# FPGA_Power_ConnectionSchematic.net
KiCad netlist of a schematic drawn in Altium Designer
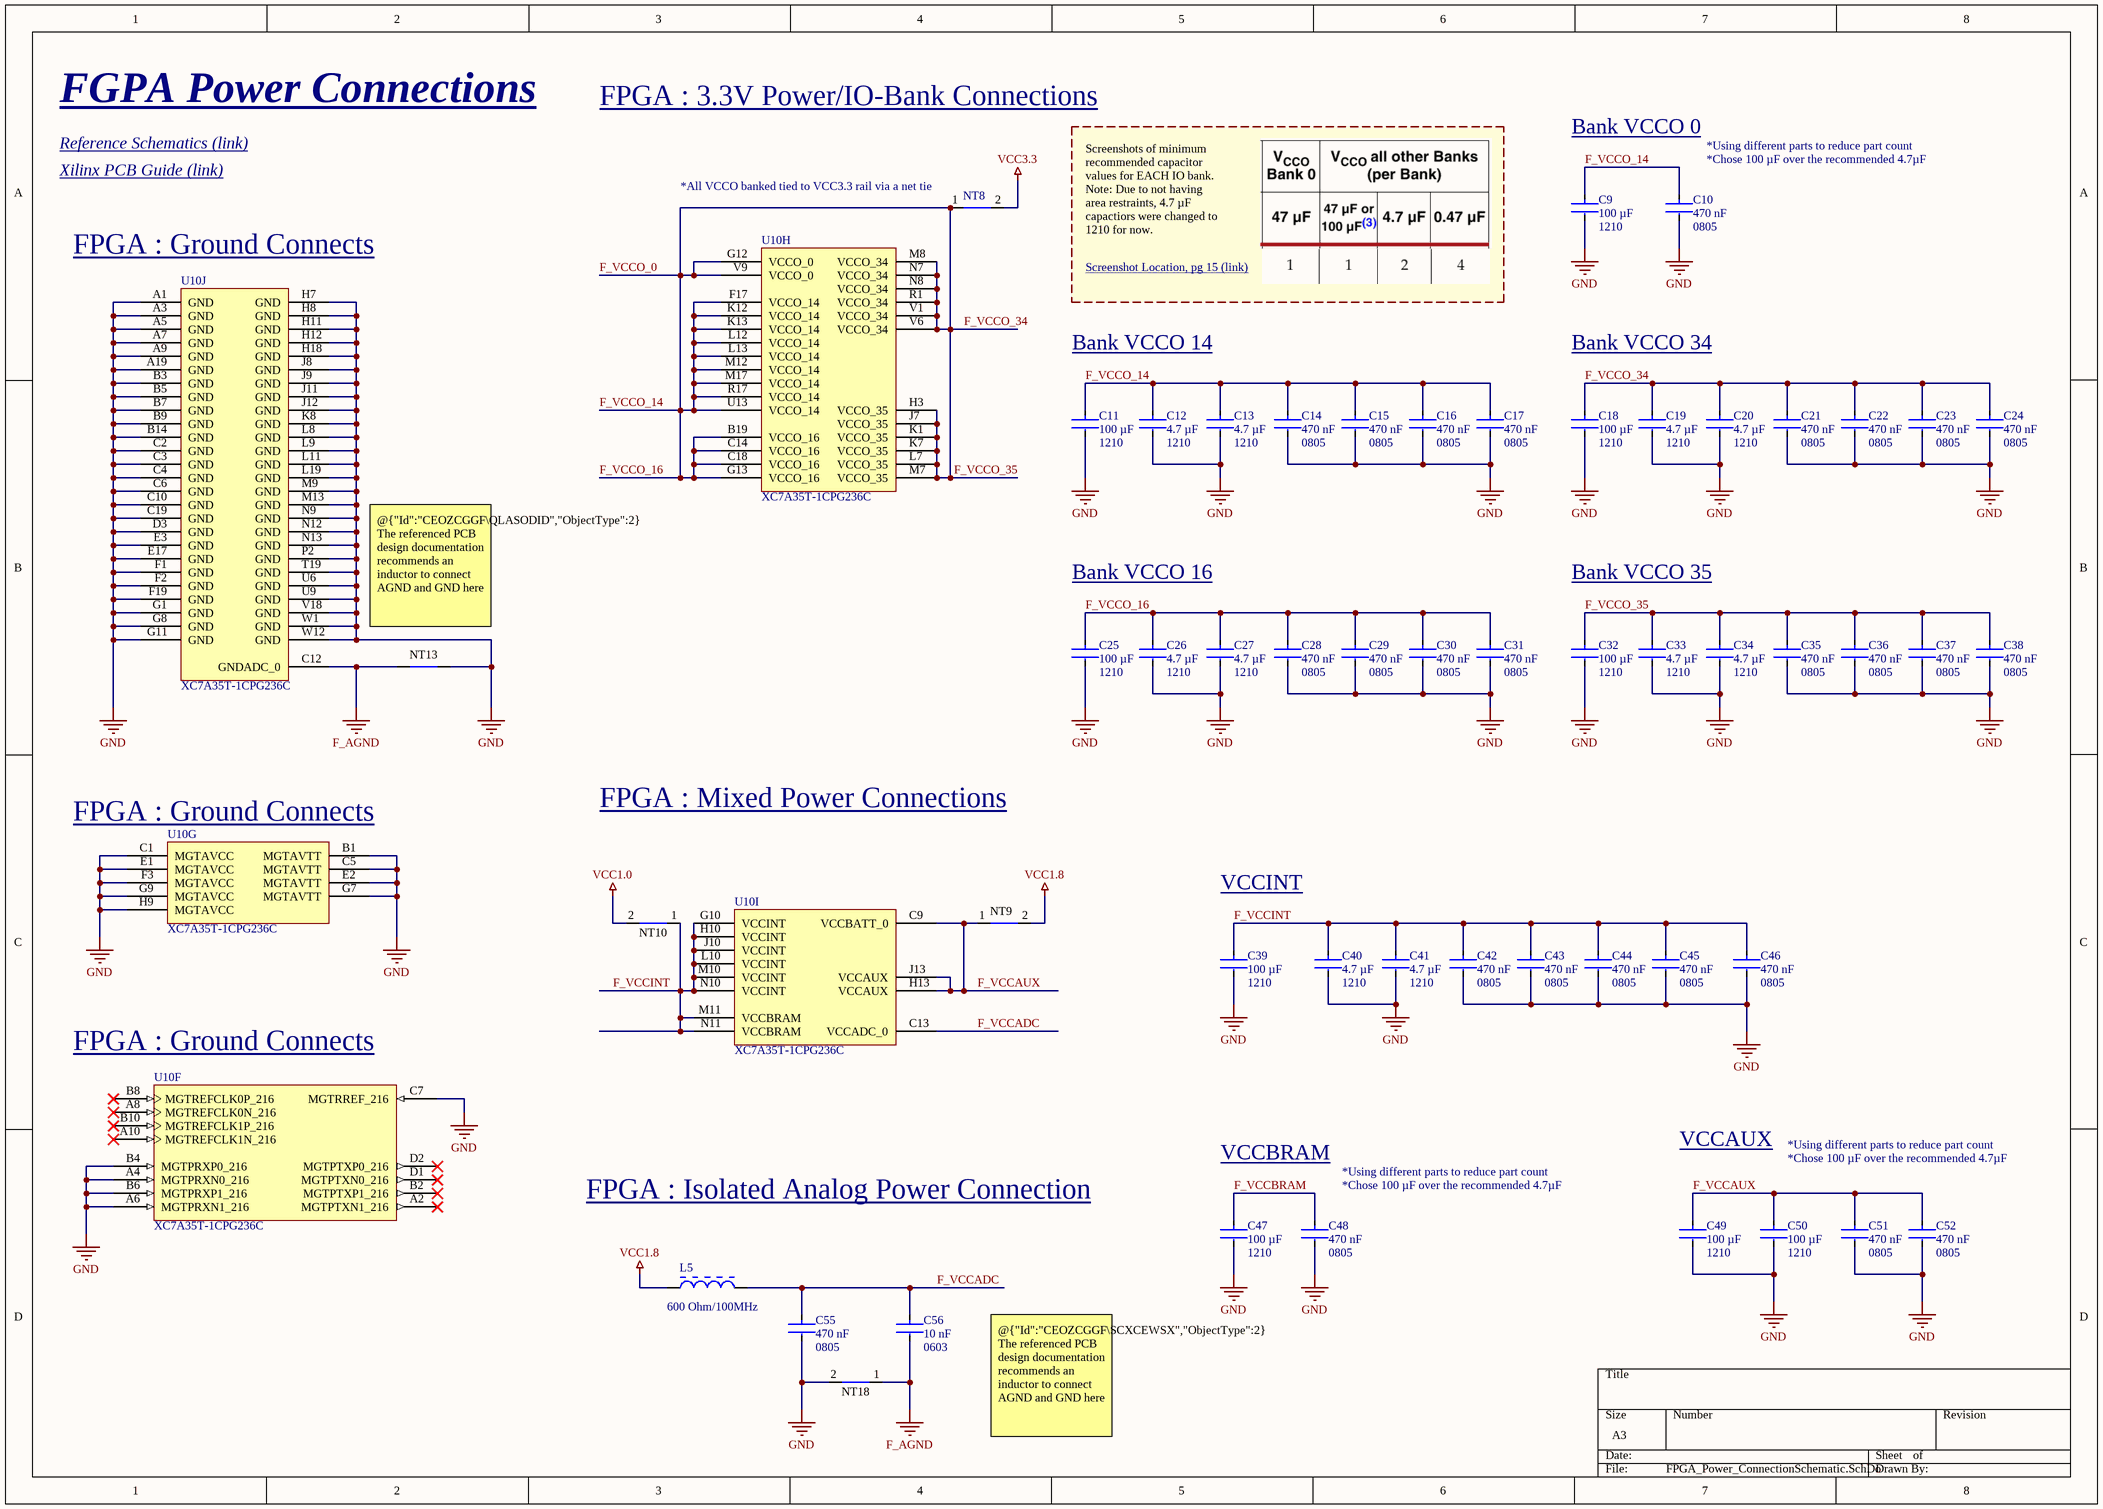
[diagram p0: FPGA_Power_ConnectionSchematic.SchDoc]

(export (version "E")
  (design (tool "Eeschema 10.0.6"))
  (components
    (comp (ref "C9")
      (value "CL32A107MQVNNNE")
      (footprint "FP-CL32-IPC_C")
      (description "CAP CER 100UF 6.3V X5R 1210")
      (fields
        (field (name "VOLTAGE") "6.3V")
        (field (name "TOLERANCE") "20%")
        (field (name "CASE CODE (IMPERIAL)") "1210")
        (field (name "CAPACITANCE") "100 µF")
      )
      (libsource (lib "Altium Content Vault") (part "b4654b650e69147ec39a6b967a45e02"))
    )
    (comp (ref "C10")
      (value "CGA4J3X7R1H474M125AE")
      (footprint "FP-CGA4J-IPC_A")
      (description "Cap Ceramic 470nF 50V X7R 20% Pad SMD 0805 +125°C Automotive T/R")
      (fields
        (field (name "CASE CODE (IMPERIAL)") "0805")
        (field (name "TOLERANCE") "20%")
        (field (name "CAPACITANCE") "470 nF")
      )
      (libsource (lib "Altium Content Vault") (part "b4654b650e69147ec39a6b967a45e02"))
    )
    (comp (ref "C11")
      (value "CL32A107MQVNNNE")
      (footprint "FP-CL32-IPC_C")
      (description "CAP CER 100UF 6.3V X5R 1210")
      (fields
        (field (name "VOLTAGE") "6.3V")
        (field (name "TOLERANCE") "20%")
        (field (name "CASE CODE (IMPERIAL)") "1210")
        (field (name "CAPACITANCE") "100 µF")
      )
      (libsource (lib "Altium Content Vault") (part "b4654b650e69147ec39a6b967a45e02"))
    )
    (comp (ref "C12")
      (value "12105C475K4Z2A")
      (footprint "FP-1210-L_3_3_0_4-W_2_5_0-IPC_B")
      (description "Automotive Ceramic Capacitor, 1210, 4.7uF, 10%, X7R, 15%, 50V")
      (fields
        (field (name "TOLERANCE") "10%")
        (field (name "CASE/PACKAGE") "1210")
        (field (name "CAPACITANCE") "4.7 µF")
      )
      (libsource (lib "Altium Content Vault") (part "b4654b650e69147ec39a6b967a45e02"))
    )
    (comp (ref "C13")
      (value "12105C475K4Z2A")
      (footprint "FP-1210-L_3_3_0_4-W_2_5_0-IPC_B")
      (description "Automotive Ceramic Capacitor, 1210, 4.7uF, 10%, X7R, 15%, 50V")
      (fields
        (field (name "TOLERANCE") "10%")
        (field (name "CASE/PACKAGE") "1210")
        (field (name "CAPACITANCE") "4.7 µF")
      )
      (libsource (lib "Altium Content Vault") (part "b4654b650e69147ec39a6b967a45e02"))
    )
    (comp (ref "C14")
      (value "CGA4J3X7R1H474M125AE")
      (footprint "FP-CGA4J-IPC_A")
      (description "Cap Ceramic 470nF 50V X7R 20% Pad SMD 0805 +125°C Automotive T/R")
      (fields
        (field (name "CASE CODE (IMPERIAL)") "0805")
        (field (name "TOLERANCE") "20%")
        (field (name "CAPACITANCE") "470 nF")
      )
      (libsource (lib "Altium Content Vault") (part "b4654b650e69147ec39a6b967a45e02"))
    )
    (comp (ref "C15")
      (value "CGA4J3X7R1H474M125AE")
      (footprint "FP-CGA4J-IPC_A")
      (description "Cap Ceramic 470nF 50V X7R 20% Pad SMD 0805 +125°C Automotive T/R")
      (fields
        (field (name "CASE CODE (IMPERIAL)") "0805")
        (field (name "TOLERANCE") "20%")
        (field (name "CAPACITANCE") "470 nF")
      )
      (libsource (lib "Altium Content Vault") (part "b4654b650e69147ec39a6b967a45e02"))
    )
    (comp (ref "C16")
      (value "CGA4J3X7R1H474M125AE")
      (footprint "FP-CGA4J-IPC_A")
      (description "Cap Ceramic 470nF 50V X7R 20% Pad SMD 0805 +125°C Automotive T/R")
      (fields
        (field (name "CASE CODE (IMPERIAL)") "0805")
        (field (name "TOLERANCE") "20%")
        (field (name "CAPACITANCE") "470 nF")
      )
      (libsource (lib "Altium Content Vault") (part "b4654b650e69147ec39a6b967a45e02"))
    )
    (comp (ref "C17")
      (value "CGA4J3X7R1H474M125AE")
      (footprint "FP-CGA4J-IPC_A")
      (description "Cap Ceramic 470nF 50V X7R 20% Pad SMD 0805 +125°C Automotive T/R")
      (fields
        (field (name "CASE CODE (IMPERIAL)") "0805")
        (field (name "TOLERANCE") "20%")
        (field (name "CAPACITANCE") "470 nF")
      )
      (libsource (lib "Altium Content Vault") (part "b4654b650e69147ec39a6b967a45e02"))
    )
    (comp (ref "C18")
      (value "CL32A107MQVNNNE")
      (footprint "FP-CL32-IPC_C")
      (description "CAP CER 100UF 6.3V X5R 1210")
      (fields
        (field (name "VOLTAGE") "6.3V")
        (field (name "TOLERANCE") "20%")
        (field (name "CASE CODE (IMPERIAL)") "1210")
        (field (name "CAPACITANCE") "100 µF")
      )
      (libsource (lib "Altium Content Vault") (part "b4654b650e69147ec39a6b967a45e02"))
    )
    (comp (ref "C19")
      (value "12105C475K4Z2A")
      (footprint "FP-1210-L_3_3_0_4-W_2_5_0-IPC_B")
      (description "Automotive Ceramic Capacitor, 1210, 4.7uF, 10%, X7R, 15%, 50V")
      (fields
        (field (name "TOLERANCE") "10%")
        (field (name "CASE/PACKAGE") "1210")
        (field (name "CAPACITANCE") "4.7 µF")
      )
      (libsource (lib "Altium Content Vault") (part "b4654b650e69147ec39a6b967a45e02"))
    )
    (comp (ref "C20")
      (value "12105C475K4Z2A")
      (footprint "FP-1210-L_3_3_0_4-W_2_5_0-IPC_B")
      (description "Automotive Ceramic Capacitor, 1210, 4.7uF, 10%, X7R, 15%, 50V")
      (fields
        (field (name "TOLERANCE") "10%")
        (field (name "CASE/PACKAGE") "1210")
        (field (name "CAPACITANCE") "4.7 µF")
      )
      (libsource (lib "Altium Content Vault") (part "b4654b650e69147ec39a6b967a45e02"))
    )
    (comp (ref "C21")
      (value "CGA4J3X7R1H474M125AE")
      (footprint "FP-CGA4J-IPC_A")
      (description "Cap Ceramic 470nF 50V X7R 20% Pad SMD 0805 +125°C Automotive T/R")
      (fields
        (field (name "CASE CODE (IMPERIAL)") "0805")
        (field (name "TOLERANCE") "20%")
        (field (name "CAPACITANCE") "470 nF")
      )
      (libsource (lib "Altium Content Vault") (part "b4654b650e69147ec39a6b967a45e02"))
    )
    (comp (ref "C22")
      (value "CGA4J3X7R1H474M125AE")
      (footprint "FP-CGA4J-IPC_A")
      (description "Cap Ceramic 470nF 50V X7R 20% Pad SMD 0805 +125°C Automotive T/R")
      (fields
        (field (name "CASE CODE (IMPERIAL)") "0805")
        (field (name "TOLERANCE") "20%")
        (field (name "CAPACITANCE") "470 nF")
      )
      (libsource (lib "Altium Content Vault") (part "b4654b650e69147ec39a6b967a45e02"))
    )
    (comp (ref "C23")
      (value "CGA4J3X7R1H474M125AE")
      (footprint "FP-CGA4J-IPC_A")
      (description "Cap Ceramic 470nF 50V X7R 20% Pad SMD 0805 +125°C Automotive T/R")
      (fields
        (field (name "CASE CODE (IMPERIAL)") "0805")
        (field (name "TOLERANCE") "20%")
        (field (name "CAPACITANCE") "470 nF")
      )
      (libsource (lib "Altium Content Vault") (part "b4654b650e69147ec39a6b967a45e02"))
    )
    (comp (ref "C24")
      (value "CGA4J3X7R1H474M125AE")
      (footprint "FP-CGA4J-IPC_A")
      (description "Cap Ceramic 470nF 50V X7R 20% Pad SMD 0805 +125°C Automotive T/R")
      (fields
        (field (name "CASE CODE (IMPERIAL)") "0805")
        (field (name "TOLERANCE") "20%")
        (field (name "CAPACITANCE") "470 nF")
      )
      (libsource (lib "Altium Content Vault") (part "b4654b650e69147ec39a6b967a45e02"))
    )
    (comp (ref "C25")
      (value "CL32A107MQVNNNE")
      (footprint "FP-CL32-IPC_C")
      (description "CAP CER 100UF 6.3V X5R 1210")
      (fields
        (field (name "VOLTAGE") "6.3V")
        (field (name "TOLERANCE") "20%")
        (field (name "CASE CODE (IMPERIAL)") "1210")
        (field (name "CAPACITANCE") "100 µF")
      )
      (libsource (lib "Altium Content Vault") (part "b4654b650e69147ec39a6b967a45e02"))
    )
    (comp (ref "C26")
      (value "12105C475K4Z2A")
      (footprint "FP-1210-L_3_3_0_4-W_2_5_0-IPC_B")
      (description "Automotive Ceramic Capacitor, 1210, 4.7uF, 10%, X7R, 15%, 50V")
      (fields
        (field (name "TOLERANCE") "10%")
        (field (name "CASE/PACKAGE") "1210")
        (field (name "CAPACITANCE") "4.7 µF")
      )
      (libsource (lib "Altium Content Vault") (part "b4654b650e69147ec39a6b967a45e02"))
    )
    (comp (ref "C27")
      (value "12105C475K4Z2A")
      (footprint "FP-1210-L_3_3_0_4-W_2_5_0-IPC_B")
      (description "Automotive Ceramic Capacitor, 1210, 4.7uF, 10%, X7R, 15%, 50V")
      (fields
        (field (name "TOLERANCE") "10%")
        (field (name "CASE/PACKAGE") "1210")
        (field (name "CAPACITANCE") "4.7 µF")
      )
      (libsource (lib "Altium Content Vault") (part "b4654b650e69147ec39a6b967a45e02"))
    )
    (comp (ref "C28")
      (value "CGA4J3X7R1H474M125AE")
      (footprint "FP-CGA4J-IPC_A")
      (description "Cap Ceramic 470nF 50V X7R 20% Pad SMD 0805 +125°C Automotive T/R")
      (fields
        (field (name "CASE CODE (IMPERIAL)") "0805")
        (field (name "TOLERANCE") "20%")
        (field (name "CAPACITANCE") "470 nF")
      )
      (libsource (lib "Altium Content Vault") (part "b4654b650e69147ec39a6b967a45e02"))
    )
    (comp (ref "C29")
      (value "CGA4J3X7R1H474M125AE")
      (footprint "FP-CGA4J-IPC_A")
      (description "Cap Ceramic 470nF 50V X7R 20% Pad SMD 0805 +125°C Automotive T/R")
      (fields
        (field (name "CASE CODE (IMPERIAL)") "0805")
        (field (name "TOLERANCE") "20%")
        (field (name "CAPACITANCE") "470 nF")
      )
      (libsource (lib "Altium Content Vault") (part "b4654b650e69147ec39a6b967a45e02"))
    )
    (comp (ref "C30")
      (value "CGA4J3X7R1H474M125AE")
      (footprint "FP-CGA4J-IPC_A")
      (description "Cap Ceramic 470nF 50V X7R 20% Pad SMD 0805 +125°C Automotive T/R")
      (fields
        (field (name "CASE CODE (IMPERIAL)") "0805")
        (field (name "TOLERANCE") "20%")
        (field (name "CAPACITANCE") "470 nF")
      )
      (libsource (lib "Altium Content Vault") (part "b4654b650e69147ec39a6b967a45e02"))
    )
    (comp (ref "C31")
      (value "CGA4J3X7R1H474M125AE")
      (footprint "FP-CGA4J-IPC_A")
      (description "Cap Ceramic 470nF 50V X7R 20% Pad SMD 0805 +125°C Automotive T/R")
      (fields
        (field (name "CASE CODE (IMPERIAL)") "0805")
        (field (name "TOLERANCE") "20%")
        (field (name "CAPACITANCE") "470 nF")
      )
      (libsource (lib "Altium Content Vault") (part "b4654b650e69147ec39a6b967a45e02"))
    )
    (comp (ref "C32")
      (value "CL32A107MQVNNNE")
      (footprint "FP-CL32-IPC_C")
      (description "CAP CER 100UF 6.3V X5R 1210")
      (fields
        (field (name "VOLTAGE") "6.3V")
        (field (name "TOLERANCE") "20%")
        (field (name "CASE CODE (IMPERIAL)") "1210")
        (field (name "CAPACITANCE") "100 µF")
      )
      (libsource (lib "Altium Content Vault") (part "b4654b650e69147ec39a6b967a45e02"))
    )
    (comp (ref "C33")
      (value "12105C475K4Z2A")
      (footprint "FP-1210-L_3_3_0_4-W_2_5_0-IPC_B")
      (description "Automotive Ceramic Capacitor, 1210, 4.7uF, 10%, X7R, 15%, 50V")
      (fields
        (field (name "TOLERANCE") "10%")
        (field (name "CASE/PACKAGE") "1210")
        (field (name "CAPACITANCE") "4.7 µF")
      )
      (libsource (lib "Altium Content Vault") (part "b4654b650e69147ec39a6b967a45e02"))
    )
    (comp (ref "C34")
      (value "12105C475K4Z2A")
      (footprint "FP-1210-L_3_3_0_4-W_2_5_0-IPC_B")
      (description "Automotive Ceramic Capacitor, 1210, 4.7uF, 10%, X7R, 15%, 50V")
      (fields
        (field (name "TOLERANCE") "10%")
        (field (name "CASE/PACKAGE") "1210")
        (field (name "CAPACITANCE") "4.7 µF")
      )
      (libsource (lib "Altium Content Vault") (part "b4654b650e69147ec39a6b967a45e02"))
    )
    (comp (ref "C35")
      (value "CGA4J3X7R1H474M125AE")
      (footprint "FP-CGA4J-IPC_A")
      (description "Cap Ceramic 470nF 50V X7R 20% Pad SMD 0805 +125°C Automotive T/R")
      (fields
        (field (name "CASE CODE (IMPERIAL)") "0805")
        (field (name "TOLERANCE") "20%")
        (field (name "CAPACITANCE") "470 nF")
      )
      (libsource (lib "Altium Content Vault") (part "b4654b650e69147ec39a6b967a45e02"))
    )
    (comp (ref "C36")
      (value "CGA4J3X7R1H474M125AE")
      (footprint "FP-CGA4J-IPC_A")
      (description "Cap Ceramic 470nF 50V X7R 20% Pad SMD 0805 +125°C Automotive T/R")
      (fields
        (field (name "CASE CODE (IMPERIAL)") "0805")
        (field (name "TOLERANCE") "20%")
        (field (name "CAPACITANCE") "470 nF")
      )
      (libsource (lib "Altium Content Vault") (part "b4654b650e69147ec39a6b967a45e02"))
    )
    (comp (ref "C37")
      (value "CGA4J3X7R1H474M125AE")
      (footprint "FP-CGA4J-IPC_A")
      (description "Cap Ceramic 470nF 50V X7R 20% Pad SMD 0805 +125°C Automotive T/R")
      (fields
        (field (name "CASE CODE (IMPERIAL)") "0805")
        (field (name "TOLERANCE") "20%")
        (field (name "CAPACITANCE") "470 nF")
      )
      (libsource (lib "Altium Content Vault") (part "b4654b650e69147ec39a6b967a45e02"))
    )
    (comp (ref "C38")
      (value "CGA4J3X7R1H474M125AE")
      (footprint "FP-CGA4J-IPC_A")
      (description "Cap Ceramic 470nF 50V X7R 20% Pad SMD 0805 +125°C Automotive T/R")
      (fields
        (field (name "CASE CODE (IMPERIAL)") "0805")
        (field (name "TOLERANCE") "20%")
        (field (name "CAPACITANCE") "470 nF")
      )
      (libsource (lib "Altium Content Vault") (part "b4654b650e69147ec39a6b967a45e02"))
    )
    (comp (ref "C39")
      (value "CL32A107MQVNNNE")
      (footprint "FP-CL32-IPC_C")
      (description "CAP CER 100UF 6.3V X5R 1210")
      (fields
        (field (name "VOLTAGE") "6.3V")
        (field (name "TOLERANCE") "20%")
        (field (name "CASE CODE (IMPERIAL)") "1210")
        (field (name "CAPACITANCE") "100 µF")
      )
      (libsource (lib "Altium Content Vault") (part "b4654b650e69147ec39a6b967a45e02"))
    )
    (comp (ref "C40")
      (value "12105C475K4Z2A")
      (footprint "FP-1210-L_3_3_0_4-W_2_5_0-IPC_B")
      (description "Automotive Ceramic Capacitor, 1210, 4.7uF, 10%, X7R, 15%, 50V")
      (fields
        (field (name "TOLERANCE") "10%")
        (field (name "CASE/PACKAGE") "1210")
        (field (name "CAPACITANCE") "4.7 µF")
      )
      (libsource (lib "Altium Content Vault") (part "b4654b650e69147ec39a6b967a45e02"))
    )
    (comp (ref "C41")
      (value "12105C475K4Z2A")
      (footprint "FP-1210-L_3_3_0_4-W_2_5_0-IPC_B")
      (description "Automotive Ceramic Capacitor, 1210, 4.7uF, 10%, X7R, 15%, 50V")
      (fields
        (field (name "TOLERANCE") "10%")
        (field (name "CASE/PACKAGE") "1210")
        (field (name "CAPACITANCE") "4.7 µF")
      )
      (libsource (lib "Altium Content Vault") (part "b4654b650e69147ec39a6b967a45e02"))
    )
    (comp (ref "C42")
      (value "CGA4J3X7R1H474M125AE")
      (footprint "FP-CGA4J-IPC_A")
      (description "Cap Ceramic 470nF 50V X7R 20% Pad SMD 0805 +125°C Automotive T/R")
      (fields
        (field (name "CASE CODE (IMPERIAL)") "0805")
        (field (name "TOLERANCE") "20%")
        (field (name "CAPACITANCE") "470 nF")
      )
      (libsource (lib "Altium Content Vault") (part "b4654b650e69147ec39a6b967a45e02"))
    )
    (comp (ref "C43")
      (value "CGA4J3X7R1H474M125AE")
      (footprint "FP-CGA4J-IPC_A")
      (description "Cap Ceramic 470nF 50V X7R 20% Pad SMD 0805 +125°C Automotive T/R")
      (fields
        (field (name "CASE CODE (IMPERIAL)") "0805")
        (field (name "TOLERANCE") "20%")
        (field (name "CAPACITANCE") "470 nF")
      )
      (libsource (lib "Altium Content Vault") (part "b4654b650e69147ec39a6b967a45e02"))
    )
    (comp (ref "C44")
      (value "CGA4J3X7R1H474M125AE")
      (footprint "FP-CGA4J-IPC_A")
      (description "Cap Ceramic 470nF 50V X7R 20% Pad SMD 0805 +125°C Automotive T/R")
      (fields
        (field (name "CASE CODE (IMPERIAL)") "0805")
        (field (name "TOLERANCE") "20%")
        (field (name "CAPACITANCE") "470 nF")
      )
      (libsource (lib "Altium Content Vault") (part "b4654b650e69147ec39a6b967a45e02"))
    )
    (comp (ref "C45")
      (value "CGA4J3X7R1H474M125AE")
      (footprint "FP-CGA4J-IPC_A")
      (description "Cap Ceramic 470nF 50V X7R 20% Pad SMD 0805 +125°C Automotive T/R")
      (fields
        (field (name "CASE CODE (IMPERIAL)") "0805")
        (field (name "TOLERANCE") "20%")
        (field (name "CAPACITANCE") "470 nF")
      )
      (libsource (lib "Altium Content Vault") (part "b4654b650e69147ec39a6b967a45e02"))
    )
    (comp (ref "C46")
      (value "CGA4J3X7R1H474M125AE")
      (footprint "FP-CGA4J-IPC_A")
      (description "Cap Ceramic 470nF 50V X7R 20% Pad SMD 0805 +125°C Automotive T/R")
      (fields
        (field (name "CASE CODE (IMPERIAL)") "0805")
        (field (name "TOLERANCE") "20%")
        (field (name "CAPACITANCE") "470 nF")
      )
      (libsource (lib "Altium Content Vault") (part "b4654b650e69147ec39a6b967a45e02"))
    )
    (comp (ref "C47")
      (value "CL32A107MQVNNNE")
      (footprint "FP-CL32-IPC_C")
      (description "CAP CER 100UF 6.3V X5R 1210")
      (fields
        (field (name "VOLTAGE") "6.3V")
        (field (name "TOLERANCE") "20%")
        (field (name "CASE CODE (IMPERIAL)") "1210")
        (field (name "CAPACITANCE") "100 µF")
      )
      (libsource (lib "Altium Content Vault") (part "b4654b650e69147ec39a6b967a45e02"))
    )
    (comp (ref "C48")
      (value "CGA4J3X7R1H474M125AE")
      (footprint "FP-CGA4J-IPC_A")
      (description "Cap Ceramic 470nF 50V X7R 20% Pad SMD 0805 +125°C Automotive T/R")
      (fields
        (field (name "CASE CODE (IMPERIAL)") "0805")
        (field (name "TOLERANCE") "20%")
        (field (name "CAPACITANCE") "470 nF")
      )
      (libsource (lib "Altium Content Vault") (part "b4654b650e69147ec39a6b967a45e02"))
    )
    (comp (ref "C49")
      (value "CL32A107MQVNNNE")
      (footprint "FP-CL32-IPC_C")
      (description "CAP CER 100UF 6.3V X5R 1210")
      (fields
        (field (name "VOLTAGE") "6.3V")
        (field (name "TOLERANCE") "20%")
        (field (name "CASE CODE (IMPERIAL)") "1210")
        (field (name "CAPACITANCE") "100 µF")
      )
      (libsource (lib "Altium Content Vault") (part "b4654b650e69147ec39a6b967a45e02"))
    )
    (comp (ref "C50")
      (value "CL32A107MQVNNNE")
      (footprint "FP-CL32-IPC_C")
      (description "CAP CER 100UF 6.3V X5R 1210")
      (fields
        (field (name "VOLTAGE") "6.3V")
        (field (name "TOLERANCE") "20%")
        (field (name "CASE CODE (IMPERIAL)") "1210")
        (field (name "CAPACITANCE") "100 µF")
      )
      (libsource (lib "Altium Content Vault") (part "b4654b650e69147ec39a6b967a45e02"))
    )
    (comp (ref "C51")
      (value "CGA4J3X7R1H474M125AE")
      (footprint "FP-CGA4J-IPC_A")
      (description "Cap Ceramic 470nF 50V X7R 20% Pad SMD 0805 +125°C Automotive T/R")
      (fields
        (field (name "CASE CODE (IMPERIAL)") "0805")
        (field (name "TOLERANCE") "20%")
        (field (name "CAPACITANCE") "470 nF")
      )
      (libsource (lib "Altium Content Vault") (part "b4654b650e69147ec39a6b967a45e02"))
    )
    (comp (ref "C52")
      (value "CGA4J3X7R1H474M125AE")
      (footprint "FP-CGA4J-IPC_A")
      (description "Cap Ceramic 470nF 50V X7R 20% Pad SMD 0805 +125°C Automotive T/R")
      (fields
        (field (name "CASE CODE (IMPERIAL)") "0805")
        (field (name "TOLERANCE") "20%")
        (field (name "CAPACITANCE") "470 nF")
      )
      (libsource (lib "Altium Content Vault") (part "b4654b650e69147ec39a6b967a45e02"))
    )
    (comp (ref "C55")
      (value "CGA4J3X7R1H474M125AE")
      (footprint "FP-CGA4J-IPC_A")
      (description "Cap Ceramic 470nF 50V X7R 20% Pad SMD 0805 +125°C Automotive T/R")
      (fields
        (field (name "CASE CODE (IMPERIAL)") "0805")
        (field (name "TOLERANCE") "20%")
        (field (name "CAPACITANCE") "470 nF")
      )
      (libsource (lib "Altium Content Vault") (part "b4654b650e69147ec39a6b967a45e02"))
    )
    (comp (ref "C56")
      (value "EMK107SD103KA-T")
      (footprint "FP-0603-L_1_6_0_1-W_0_8_0-MFG")
      (description "None")
      (fields
        (field (name "CASE CODE (IMPERIAL)") "0603")
        (field (name "TOLERANCE") "10%")
        (field (name "CAPACITANCE") "10 nF")
      )
      (libsource (lib "Altium Content Vault") (part "02cd4be3c70576c341d710602a673aa"))
    )
    (comp (ref "L5")
      (value "SRN3015-3R3M")
      (footprint "BOUR-SRN3015-2_V")
      (fields (field (name "MANUFACTURER") "Bourns") (field (name "OHMATFREQ") "600 Ohm/100MHz"))
      (libsource (lib "Altium Content Vault") (part "BOUR-IND-2A"))
    )
    (comp (ref "NT8")
      (value "NetTieSMD_2Line")
      (footprint "NetTieSMD_2Line-Footprint-1")
      (description "Net tie for a small straigth net tie.")
      (libsource (lib "Personal Workspace") (part "NetTieSMD_2Line-Symbol-1"))
    )
    (comp (ref "NT9")
      (value "NetTieSMD_2Line")
      (footprint "NetTieSMD_2Line-Footprint-1")
      (description "Net tie for a small straigth net tie.")
      (libsource (lib "Personal Workspace") (part "NetTieSMD_2Line-Symbol-1"))
    )
    (comp (ref "NT10")
      (value "NetTieSMD_2Line")
      (footprint "NetTieSMD_2Line-Footprint-1")
      (description "Net tie for a small straigth net tie.")
      (libsource (lib "Personal Workspace") (part "NetTieSMD_2Line-Symbol-1"))
    )
    (comp (ref "NT13")
      (value "NetTieSMD_2Line")
      (footprint "NetTieSMD_2Line-Footprint-1")
      (description "Net tie for a small straigth net tie.")
      (libsource (lib "") (part "NetTieSMD_2Line-Symbol-1_1"))
    )
    (comp (ref "NT18")
      (value "NetTieSMD_2Line")
      (footprint "NetTieSMD_2Line-Footprint-1")
      (description "Net tie for a small straigth net tie.")
      (libsource (lib "Personal Workspace") (part "NetTieSMD_2Line-Symbol-1"))
    )
    (comp (ref "U10")
      (value "XC7A35T-1CPG236C")
      (footprint "CPG236")
      (description "Artix-7 FPGA, 106 User I/Os, 2 GTP, 238-Ball BGA, Speed Grade 1, Commercial Grade, Pb-Free")
      (fields (field (name "MANUFACTURER") "Xilinx"))
      (libsource (lib "Altium Content Vault") (part "XLNX-XC7A35T-CPG236"))
    )
  )
  (nets
    (net (code "1") (name "/F_VCCADC") (class "Default")
      (node (ref "C55") (pin "1") (pinfunction "1_1") (pintype "passive"))
      (node (ref "C56") (pin "1") (pinfunction "1_1") (pintype "passive"))
      (node (ref "L5") (pin "1") (pinfunction "1_1") (pintype "passive"))
      (node (ref "U10") (pin "C13") (pinfunction "VCCADC_0_C13") (pintype "power_in"))
    )
    (net (code "2") (name "/F_VCCAUX") (class "Default")
      (node (ref "C49") (pin "1") (pinfunction "1_1") (pintype "passive"))
      (node (ref "C50") (pin "1") (pinfunction "1_1") (pintype "passive"))
      (node (ref "C51") (pin "1") (pinfunction "1_1") (pintype "passive"))
      (node (ref "C52") (pin "1") (pinfunction "1_1") (pintype "passive"))
      (node (ref "NT9") (pin "1") (pinfunction "1_1") (pintype "passive"))
      (node (ref "U10") (pin "C9") (pinfunction "VCCBATT_0_C9") (pintype "power_in"))
      (node (ref "U10") (pin "H13") (pinfunction "VCCAUX_H13") (pintype "power_in"))
      (node (ref "U10") (pin "J13") (pinfunction "VCCAUX_J13") (pintype "power_in"))
    )
    (net (code "3") (name "/F_VCCBRAM") (class "Default")
      (node (ref "C47") (pin "1") (pinfunction "1_1") (pintype "passive"))
      (node (ref "C48") (pin "1") (pinfunction "1_1") (pintype "passive"))
    )
    (net (code "4") (name "/F_VCCINT") (class "Default")
      (node (ref "C39") (pin "1") (pinfunction "1_1") (pintype "passive"))
      (node (ref "C40") (pin "1") (pinfunction "1_1") (pintype "passive"))
      (node (ref "C41") (pin "1") (pinfunction "1_1") (pintype "passive"))
      (node (ref "C42") (pin "1") (pinfunction "1_1") (pintype "passive"))
      (node (ref "C43") (pin "1") (pinfunction "1_1") (pintype "passive"))
      (node (ref "C44") (pin "1") (pinfunction "1_1") (pintype "passive"))
      (node (ref "C45") (pin "1") (pinfunction "1_1") (pintype "passive"))
      (node (ref "C46") (pin "1") (pinfunction "1_1") (pintype "passive"))
      (node (ref "NT10") (pin "1") (pinfunction "1_1") (pintype "passive"))
      (node (ref "U10") (pin "G10") (pinfunction "VCCINT_G10") (pintype "power_in"))
      (node (ref "U10") (pin "H10") (pinfunction "VCCINT_H10") (pintype "power_in"))
      (node (ref "U10") (pin "J10") (pinfunction "VCCINT_J10") (pintype "power_in"))
      (node (ref "U10") (pin "L10") (pinfunction "VCCINT_L10") (pintype "power_in"))
      (node (ref "U10") (pin "M10") (pinfunction "VCCINT_M10") (pintype "power_in"))
      (node (ref "U10") (pin "M11") (pinfunction "VCCBRAM_M11") (pintype "power_in"))
      (node (ref "U10") (pin "N10") (pinfunction "VCCINT_N10") (pintype "power_in"))
      (node (ref "U10") (pin "N11") (pinfunction "VCCBRAM_N11") (pintype "power_in"))
    )
    (net (code "5") (name "/F_VCCO_0") (class "Default")
      (node (ref "C10") (pin "1") (pinfunction "1_1") (pintype "passive"))
      (node (ref "C11") (pin "1") (pinfunction "1_1") (pintype "passive"))
      (node (ref "C12") (pin "1") (pinfunction "1_1") (pintype "passive"))
      (node (ref "C13") (pin "1") (pinfunction "1_1") (pintype "passive"))
      (node (ref "C14") (pin "1") (pinfunction "1_1") (pintype "passive"))
      (node (ref "C15") (pin "1") (pinfunction "1_1") (pintype "passive"))
      (node (ref "C16") (pin "1") (pinfunction "1_1") (pintype "passive"))
      (node (ref "C17") (pin "1") (pinfunction "1_1") (pintype "passive"))
      (node (ref "C18") (pin "1") (pinfunction "1_1") (pintype "passive"))
      (node (ref "C19") (pin "1") (pinfunction "1_1") (pintype "passive"))
      (node (ref "C20") (pin "1") (pinfunction "1_1") (pintype "passive"))
      (node (ref "C21") (pin "1") (pinfunction "1_1") (pintype "passive"))
      (node (ref "C22") (pin "1") (pinfunction "1_1") (pintype "passive"))
      (node (ref "C23") (pin "1") (pinfunction "1_1") (pintype "passive"))
      (node (ref "C24") (pin "1") (pinfunction "1_1") (pintype "passive"))
      (node (ref "C25") (pin "1") (pinfunction "1_1") (pintype "passive"))
      (node (ref "C26") (pin "1") (pinfunction "1_1") (pintype "passive"))
      (node (ref "C27") (pin "1") (pinfunction "1_1") (pintype "passive"))
      (node (ref "C28") (pin "1") (pinfunction "1_1") (pintype "passive"))
      (node (ref "C29") (pin "1") (pinfunction "1_1") (pintype "passive"))
      (node (ref "C30") (pin "1") (pinfunction "1_1") (pintype "passive"))
      (node (ref "C31") (pin "1") (pinfunction "1_1") (pintype "passive"))
      (node (ref "C32") (pin "1") (pinfunction "1_1") (pintype "passive"))
      (node (ref "C33") (pin "1") (pinfunction "1_1") (pintype "passive"))
      (node (ref "C34") (pin "1") (pinfunction "1_1") (pintype "passive"))
      (node (ref "C35") (pin "1") (pinfunction "1_1") (pintype "passive"))
      (node (ref "C36") (pin "1") (pinfunction "1_1") (pintype "passive"))
      (node (ref "C37") (pin "1") (pinfunction "1_1") (pintype "passive"))
      (node (ref "C38") (pin "1") (pinfunction "1_1") (pintype "passive"))
      (node (ref "C9") (pin "1") (pinfunction "1_1") (pintype "passive"))
      (node (ref "NT8") (pin "1") (pinfunction "1_1") (pintype "passive"))
      (node (ref "U10") (pin "B19") (pinfunction "VCCO_16_B19") (pintype "power_in"))
      (node (ref "U10") (pin "C14") (pinfunction "VCCO_16_C14") (pintype "power_in"))
      (node (ref "U10") (pin "C18") (pinfunction "VCCO_16_C18") (pintype "power_in"))
      (node (ref "U10") (pin "F17") (pinfunction "VCCO_14_F17") (pintype "power_in"))
      (node (ref "U10") (pin "G12") (pinfunction "VCCO_0_G12") (pintype "power_in"))
      (node (ref "U10") (pin "G13") (pinfunction "VCCO_16_G13") (pintype "power_in"))
      (node (ref "U10") (pin "H3") (pinfunction "VCCO_35_H3") (pintype "power_in"))
      (node (ref "U10") (pin "J7") (pinfunction "VCCO_35_J7") (pintype "power_in"))
      (node (ref "U10") (pin "K1") (pinfunction "VCCO_35_K1") (pintype "power_in"))
      (node (ref "U10") (pin "K12") (pinfunction "VCCO_14_K12") (pintype "power_in"))
      (node (ref "U10") (pin "K13") (pinfunction "VCCO_14_K13") (pintype "power_in"))
      (node (ref "U10") (pin "K7") (pinfunction "VCCO_35_K7") (pintype "power_in"))
      (node (ref "U10") (pin "L12") (pinfunction "VCCO_14_L12") (pintype "power_in"))
      (node (ref "U10") (pin "L13") (pinfunction "VCCO_14_L13") (pintype "power_in"))
      (node (ref "U10") (pin "L7") (pinfunction "VCCO_35_L7") (pintype "power_in"))
      (node (ref "U10") (pin "M12") (pinfunction "VCCO_14_M12") (pintype "power_in"))
      (node (ref "U10") (pin "M17") (pinfunction "VCCO_14_M17") (pintype "power_in"))
      (node (ref "U10") (pin "M7") (pinfunction "VCCO_35_M7") (pintype "power_in"))
      (node (ref "U10") (pin "M8") (pinfunction "VCCO_34_M8") (pintype "power_in"))
      (node (ref "U10") (pin "N7") (pinfunction "VCCO_34_N7") (pintype "power_in"))
      (node (ref "U10") (pin "N8") (pinfunction "VCCO_34_N8") (pintype "power_in"))
      (node (ref "U10") (pin "R1") (pinfunction "VCCO_34_R1") (pintype "power_in"))
      (node (ref "U10") (pin "R17") (pinfunction "VCCO_14_R17") (pintype "power_in"))
      (node (ref "U10") (pin "U13") (pinfunction "VCCO_14_U13") (pintype "power_in"))
      (node (ref "U10") (pin "V1") (pinfunction "VCCO_34_V1") (pintype "power_in"))
      (node (ref "U10") (pin "V6") (pinfunction "VCCO_34_V6") (pintype "power_in"))
      (node (ref "U10") (pin "V9") (pinfunction "VCCO_0_V9") (pintype "power_in"))
    )
    (net (code "6") (name "F_AGND") (class "Default")
      (node (ref "C56") (pin "2") (pinfunction "2_2") (pintype "passive"))
      (node (ref "NT13") (pin "1") (pinfunction "1_1") (pintype "passive"))
      (node (ref "NT18") (pin "1") (pinfunction "1_1") (pintype "passive"))
      (node (ref "U10") (pin "C12") (pinfunction "GNDADC_0_C12") (pintype "power_in"))
    )
    (net (code "7") (name "GND") (class "Default")
      (node (ref "C10") (pin "2") (pinfunction "2_2") (pintype "passive"))
      (node (ref "C11") (pin "2") (pinfunction "2_2") (pintype "passive"))
      (node (ref "C12") (pin "2") (pinfunction "2_2") (pintype "passive"))
      (node (ref "C13") (pin "2") (pinfunction "2_2") (pintype "passive"))
      (node (ref "C14") (pin "2") (pinfunction "2_2") (pintype "passive"))
      (node (ref "C15") (pin "2") (pinfunction "2_2") (pintype "passive"))
      (node (ref "C16") (pin "2") (pinfunction "2_2") (pintype "passive"))
      (node (ref "C17") (pin "2") (pinfunction "2_2") (pintype "passive"))
      (node (ref "C18") (pin "2") (pinfunction "2_2") (pintype "passive"))
      (node (ref "C19") (pin "2") (pinfunction "2_2") (pintype "passive"))
      (node (ref "C20") (pin "2") (pinfunction "2_2") (pintype "passive"))
      (node (ref "C21") (pin "2") (pinfunction "2_2") (pintype "passive"))
      (node (ref "C22") (pin "2") (pinfunction "2_2") (pintype "passive"))
      (node (ref "C23") (pin "2") (pinfunction "2_2") (pintype "passive"))
      (node (ref "C24") (pin "2") (pinfunction "2_2") (pintype "passive"))
      (node (ref "C25") (pin "2") (pinfunction "2_2") (pintype "passive"))
      (node (ref "C26") (pin "2") (pinfunction "2_2") (pintype "passive"))
      (node (ref "C27") (pin "2") (pinfunction "2_2") (pintype "passive"))
      (node (ref "C28") (pin "2") (pinfunction "2_2") (pintype "passive"))
      (node (ref "C29") (pin "2") (pinfunction "2_2") (pintype "passive"))
      (node (ref "C30") (pin "2") (pinfunction "2_2") (pintype "passive"))
      (node (ref "C31") (pin "2") (pinfunction "2_2") (pintype "passive"))
      (node (ref "C32") (pin "2") (pinfunction "2_2") (pintype "passive"))
      (node (ref "C33") (pin "2") (pinfunction "2_2") (pintype "passive"))
      (node (ref "C34") (pin "2") (pinfunction "2_2") (pintype "passive"))
      (node (ref "C35") (pin "2") (pinfunction "2_2") (pintype "passive"))
      (node (ref "C36") (pin "2") (pinfunction "2_2") (pintype "passive"))
      (node (ref "C37") (pin "2") (pinfunction "2_2") (pintype "passive"))
      (node (ref "C38") (pin "2") (pinfunction "2_2") (pintype "passive"))
      (node (ref "C39") (pin "2") (pinfunction "2_2") (pintype "passive"))
      (node (ref "C40") (pin "2") (pinfunction "2_2") (pintype "passive"))
      (node (ref "C41") (pin "2") (pinfunction "2_2") (pintype "passive"))
      (node (ref "C42") (pin "2") (pinfunction "2_2") (pintype "passive"))
      (node (ref "C43") (pin "2") (pinfunction "2_2") (pintype "passive"))
      (node (ref "C44") (pin "2") (pinfunction "2_2") (pintype "passive"))
      (node (ref "C45") (pin "2") (pinfunction "2_2") (pintype "passive"))
      (node (ref "C46") (pin "2") (pinfunction "2_2") (pintype "passive"))
      (node (ref "C47") (pin "2") (pinfunction "2_2") (pintype "passive"))
      (node (ref "C48") (pin "2") (pinfunction "2_2") (pintype "passive"))
      (node (ref "C49") (pin "2") (pinfunction "2_2") (pintype "passive"))
      (node (ref "C50") (pin "2") (pinfunction "2_2") (pintype "passive"))
      (node (ref "C51") (pin "2") (pinfunction "2_2") (pintype "passive"))
      (node (ref "C52") (pin "2") (pinfunction "2_2") (pintype "passive"))
      (node (ref "C55") (pin "2") (pinfunction "2_2") (pintype "passive"))
      (node (ref "C9") (pin "2") (pinfunction "2_2") (pintype "passive"))
      (node (ref "NT13") (pin "2") (pinfunction "2_2") (pintype "passive"))
      (node (ref "NT18") (pin "2") (pinfunction "2_2") (pintype "passive"))
      (node (ref "U10") (pin "A1") (pinfunction "GND_A1") (pintype "power_in"))
      (node (ref "U10") (pin "A19") (pinfunction "GND_A19") (pintype "power_in"))
      (node (ref "U10") (pin "A3") (pinfunction "GND_A3") (pintype "power_in"))
      (node (ref "U10") (pin "A4") (pinfunction "MGTPRXN0_216_A4") (pintype "input"))
      (node (ref "U10") (pin "A5") (pinfunction "GND_A5") (pintype "power_in"))
      (node (ref "U10") (pin "A6") (pinfunction "MGTPRXN1_216_A6") (pintype "input"))
      (node (ref "U10") (pin "A7") (pinfunction "GND_A7") (pintype "power_in"))
      (node (ref "U10") (pin "A9") (pinfunction "GND_A9") (pintype "power_in"))
      (node (ref "U10") (pin "B1") (pinfunction "MGTAVTT_B1") (pintype "power_in"))
      (node (ref "U10") (pin "B14") (pinfunction "GND_B14") (pintype "power_in"))
      (node (ref "U10") (pin "B3") (pinfunction "GND_B3") (pintype "power_in"))
      (node (ref "U10") (pin "B4") (pinfunction "MGTPRXP0_216_B4") (pintype "input"))
      (node (ref "U10") (pin "B5") (pinfunction "GND_B5") (pintype "power_in"))
      (node (ref "U10") (pin "B6") (pinfunction "MGTPRXP1_216_B6") (pintype "input"))
      (node (ref "U10") (pin "B7") (pinfunction "GND_B7") (pintype "power_in"))
      (node (ref "U10") (pin "B9") (pinfunction "GND_B9") (pintype "power_in"))
      (node (ref "U10") (pin "C1") (pinfunction "MGTAVCC_C1") (pintype "power_in"))
      (node (ref "U10") (pin "C10") (pinfunction "GND_C10") (pintype "power_in"))
      (node (ref "U10") (pin "C19") (pinfunction "GND_C19") (pintype "power_in"))
      (node (ref "U10") (pin "C2") (pinfunction "GND_C2") (pintype "power_in"))
      (node (ref "U10") (pin "C3") (pinfunction "GND_C3") (pintype "power_in"))
      (node (ref "U10") (pin "C4") (pinfunction "GND_C4") (pintype "power_in"))
      (node (ref "U10") (pin "C5") (pinfunction "MGTAVTT_C5") (pintype "power_in"))
      (node (ref "U10") (pin "C6") (pinfunction "GND_C6") (pintype "power_in"))
      (node (ref "U10") (pin "C7") (pinfunction "MGTRREF_216_C7") (pintype "input"))
      (node (ref "U10") (pin "D3") (pinfunction "GND_D3") (pintype "power_in"))
      (node (ref "U10") (pin "E1") (pinfunction "MGTAVCC_E1") (pintype "power_in"))
      (node (ref "U10") (pin "E17") (pinfunction "GND_E17") (pintype "power_in"))
      (node (ref "U10") (pin "E2") (pinfunction "MGTAVTT_E2") (pintype "power_in"))
      (node (ref "U10") (pin "E3") (pinfunction "GND_E3") (pintype "power_in"))
      (node (ref "U10") (pin "F1") (pinfunction "GND_F1") (pintype "power_in"))
      (node (ref "U10") (pin "F19") (pinfunction "GND_F19") (pintype "power_in"))
      (node (ref "U10") (pin "F2") (pinfunction "GND_F2") (pintype "power_in"))
      (node (ref "U10") (pin "F3") (pinfunction "MGTAVCC_F3") (pintype "power_in"))
      (node (ref "U10") (pin "G1") (pinfunction "GND_G1") (pintype "power_in"))
      (node (ref "U10") (pin "G11") (pinfunction "GND_G11") (pintype "power_in"))
      (node (ref "U10") (pin "G7") (pinfunction "MGTAVTT_G7") (pintype "power_in"))
      (node (ref "U10") (pin "G8") (pinfunction "GND_G8") (pintype "power_in"))
      (node (ref "U10") (pin "G9") (pinfunction "MGTAVCC_G9") (pintype "power_in"))
      (node (ref "U10") (pin "H11") (pinfunction "GND_H11") (pintype "power_in"))
      (node (ref "U10") (pin "H12") (pinfunction "GND_H12") (pintype "power_in"))
      (node (ref "U10") (pin "H18") (pinfunction "GND_H18") (pintype "power_in"))
      (node (ref "U10") (pin "H7") (pinfunction "GND_H7") (pintype "power_in"))
      (node (ref "U10") (pin "H8") (pinfunction "GND_H8") (pintype "power_in"))
      (node (ref "U10") (pin "H9") (pinfunction "MGTAVCC_H9") (pintype "power_in"))
      (node (ref "U10") (pin "J11") (pinfunction "GND_J11") (pintype "power_in"))
      (node (ref "U10") (pin "J12") (pinfunction "GND_J12") (pintype "power_in"))
      (node (ref "U10") (pin "J8") (pinfunction "GND_J8") (pintype "power_in"))
      (node (ref "U10") (pin "J9") (pinfunction "GND_J9") (pintype "power_in"))
      (node (ref "U10") (pin "K8") (pinfunction "GND_K8") (pintype "power_in"))
      (node (ref "U10") (pin "L11") (pinfunction "GND_L11") (pintype "power_in"))
      (node (ref "U10") (pin "L19") (pinfunction "GND_L19") (pintype "power_in"))
      (node (ref "U10") (pin "L8") (pinfunction "GND_L8") (pintype "power_in"))
      (node (ref "U10") (pin "L9") (pinfunction "GND_L9") (pintype "power_in"))
      (node (ref "U10") (pin "M13") (pinfunction "GND_M13") (pintype "power_in"))
      (node (ref "U10") (pin "M9") (pinfunction "GND_M9") (pintype "power_in"))
      (node (ref "U10") (pin "N12") (pinfunction "GND_N12") (pintype "power_in"))
      (node (ref "U10") (pin "N13") (pinfunction "GND_N13") (pintype "power_in"))
      (node (ref "U10") (pin "N9") (pinfunction "GND_N9") (pintype "power_in"))
      (node (ref "U10") (pin "P2") (pinfunction "GND_P2") (pintype "power_in"))
      (node (ref "U10") (pin "T19") (pinfunction "GND_T19") (pintype "power_in"))
      (node (ref "U10") (pin "U6") (pinfunction "GND_U6") (pintype "power_in"))
      (node (ref "U10") (pin "U9") (pinfunction "GND_U9") (pintype "power_in"))
      (node (ref "U10") (pin "V18") (pinfunction "GND_V18") (pintype "power_in"))
      (node (ref "U10") (pin "W1") (pinfunction "GND_W1") (pintype "power_in"))
      (node (ref "U10") (pin "W12") (pinfunction "GND_W12") (pintype "power_in"))
    )
    (net (code "8") (name "VCC1.0") (class "Default")
      (node (ref "NT10") (pin "2") (pinfunction "2_2") (pintype "passive"))
    )
    (net (code "9") (name "VCC1.8") (class "Default")
      (node (ref "L5") (pin "2") (pinfunction "2_2") (pintype "passive"))
      (node (ref "NT9") (pin "2") (pinfunction "2_2") (pintype "passive"))
    )
    (net (code "10") (name "VCC3.3") (class "Default")
      (node (ref "NT8") (pin "2") (pinfunction "2_2") (pintype "passive"))
    )
    (net (code "11") (name "unconnected-(U10F-MGTPTXN0_216-PadD1)") (class "Default")
      (node (ref "U10") (pin "D1") (pinfunction "MGTPTXN0_216_D1") (pintype "output+no_connect"))
    )
    (net (code "12") (name "unconnected-(U10F-MGTPTXN1_216-PadA2)") (class "Default")
      (node (ref "U10") (pin "A2") (pinfunction "MGTPTXN1_216_A2") (pintype "output+no_connect"))
    )
    (net (code "13") (name "unconnected-(U10F-MGTPTXP0_216-PadD2)") (class "Default")
      (node (ref "U10") (pin "D2") (pinfunction "MGTPTXP0_216_D2") (pintype "output+no_connect"))
    )
    (net (code "14") (name "unconnected-(U10F-MGTPTXP1_216-PadB2)") (class "Default")
      (node (ref "U10") (pin "B2") (pinfunction "MGTPTXP1_216_B2") (pintype "output+no_connect"))
    )
    (net (code "15") (name "unconnected-(U10F-MGTREFCLK0N_216-PadA8)") (class "Default")
      (node (ref "U10") (pin "A8") (pinfunction "MGTREFCLK0N_216_A8") (pintype "input+no_connect"))
    )
    (net (code "16") (name "unconnected-(U10F-MGTREFCLK0P_216-PadB8)") (class "Default")
      (node (ref "U10") (pin "B8") (pinfunction "MGTREFCLK0P_216_B8") (pintype "input+no_connect"))
    )
    (net (code "17") (name "unconnected-(U10F-MGTREFCLK1N_216-PadA10)") (class "Default")
      (node (ref "U10") (pin "A10") (pinfunction "MGTREFCLK1N_216_A10") (pintype "input+no_connect"))
    )
    (net (code "18") (name "unconnected-(U10F-MGTREFCLK1P_216-PadB10)") (class "Default")
      (node (ref "U10") (pin "B10") (pinfunction "MGTREFCLK1P_216_B10") (pintype "input+no_connect"))
    )
  )
)
